# ir_array_final.net
KiCad netlist of a schematic drawn in EAGLE
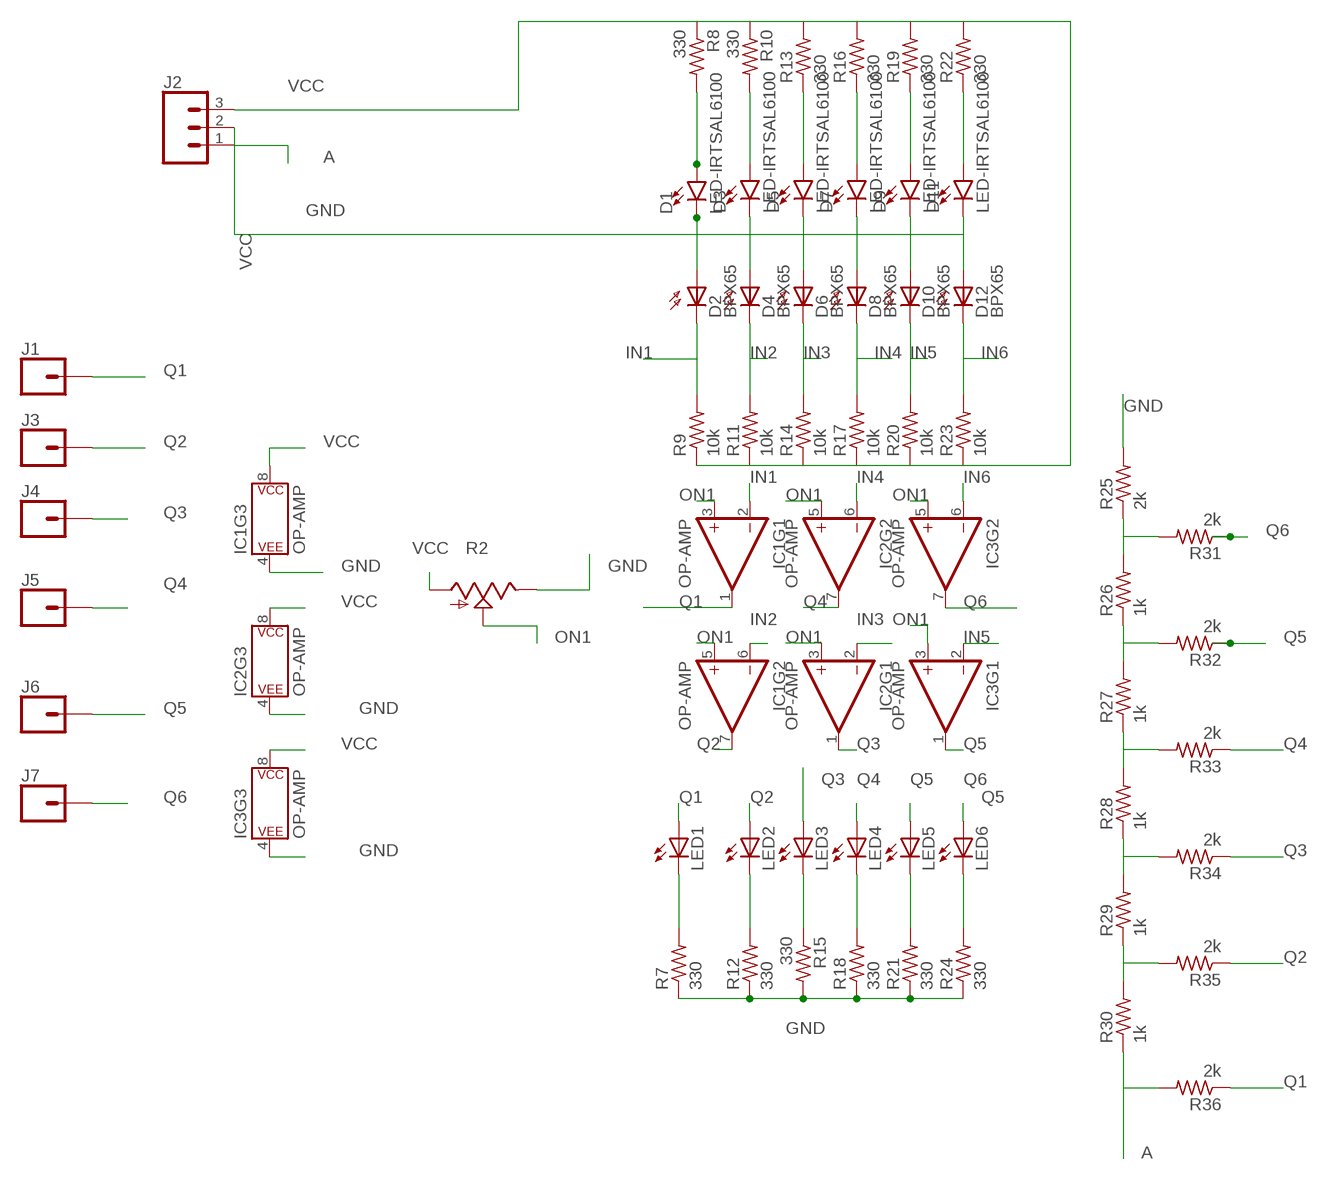
[diagram p0: schematic, sheet 1]

(export (version "E")
  (design (tool "Eeschema 10.0.6"))
  (components
    (comp (ref "D1")
      (value "LED-IRTSAL6100")
      (footprint "eagle-import:LED_5MM")
      (libsource (lib "eagle-import") (part "LED-IRTSAL6100"))
    )
    (comp (ref "D2")
      (value "BPX65")
      (footprint "eagle-import:BPX65")
      (fields (field (name "MPN") "BPX65."))
      (libsource (lib "eagle-import") (part "BPX65"))
    )
    (comp (ref "D3")
      (value "LED-IRTSAL6100")
      (footprint "eagle-import:LED_5MM")
      (libsource (lib "eagle-import") (part "LED-IRTSAL6100"))
    )
    (comp (ref "D4")
      (value "BPX65")
      (footprint "eagle-import:BPX65")
      (fields (field (name "MPN") "BPX65."))
      (libsource (lib "eagle-import") (part "BPX65"))
    )
    (comp (ref "D5")
      (value "LED-IRTSAL6100")
      (footprint "eagle-import:LED_5MM")
      (libsource (lib "eagle-import") (part "LED-IRTSAL6100"))
    )
    (comp (ref "D6")
      (value "BPX65")
      (footprint "eagle-import:BPX65")
      (fields (field (name "MPN") "BPX65."))
      (libsource (lib "eagle-import") (part "BPX65"))
    )
    (comp (ref "D7")
      (value "LED-IRTSAL6100")
      (footprint "eagle-import:LED_5MM")
      (libsource (lib "eagle-import") (part "LED-IRTSAL6100"))
    )
    (comp (ref "D8")
      (value "BPX65")
      (footprint "eagle-import:BPX65")
      (fields (field (name "MPN") "BPX65."))
      (libsource (lib "eagle-import") (part "BPX65"))
    )
    (comp (ref "D9")
      (value "LED-IRTSAL6100")
      (footprint "eagle-import:LED_5MM")
      (libsource (lib "eagle-import") (part "LED-IRTSAL6100"))
    )
    (comp (ref "D10")
      (value "BPX65")
      (footprint "eagle-import:BPX65")
      (fields (field (name "MPN") "BPX65."))
      (libsource (lib "eagle-import") (part "BPX65"))
    )
    (comp (ref "D11")
      (value "LED-IRTSAL6100")
      (footprint "eagle-import:LED_5MM")
      (libsource (lib "eagle-import") (part "LED-IRTSAL6100"))
    )
    (comp (ref "D12")
      (value "BPX65")
      (footprint "eagle-import:BPX65")
      (fields (field (name "MPN") "BPX65."))
      (libsource (lib "eagle-import") (part "BPX65"))
    )
    (comp (ref "IC1")
      (value "OP-AMP")
      (footprint "eagle-import:DIP08")
      (libsource (lib "eagle-import") (part "OPAMP-DUALDIP"))
    )
    (comp (ref "IC2")
      (value "OP-AMP")
      (footprint "eagle-import:DIP08")
      (libsource (lib "eagle-import") (part "OPAMP-DUALDIP"))
    )
    (comp (ref "IC3")
      (value "OP-AMP")
      (footprint "eagle-import:DIP08")
      (libsource (lib "eagle-import") (part "OPAMP-DUALDIP"))
    )
    (comp (ref "J1")
      (value "CONN_01")
      (footprint "eagle-import:1X01")
      (libsource (lib "eagle-import") (part "CONN_01"))
    )
    (comp (ref "J2")
      (value "CONN_03")
      (footprint "eagle-import:1X03")
      (libsource (lib "eagle-import") (part "CONN_03"))
    )
    (comp (ref "J3")
      (value "CONN_01")
      (footprint "eagle-import:1X01")
      (libsource (lib "eagle-import") (part "CONN_01"))
    )
    (comp (ref "J4")
      (value "CONN_01")
      (footprint "eagle-import:1X01")
      (libsource (lib "eagle-import") (part "CONN_01"))
    )
    (comp (ref "J5")
      (value "CONN_01")
      (footprint "eagle-import:1X01")
      (libsource (lib "eagle-import") (part "CONN_01"))
    )
    (comp (ref "J6")
      (value "CONN_01")
      (footprint "eagle-import:1X01")
      (libsource (lib "eagle-import") (part "CONN_01"))
    )
    (comp (ref "J7")
      (value "CONN_01")
      (footprint "eagle-import:1X01")
      (libsource (lib "eagle-import") (part "CONN_01"))
    )
    (comp (ref "LED1")
      (value "LED3MM")
      (footprint "eagle-import:LED3MM")
      (libsource (lib "eagle-import") (part "LED3MM"))
    )
    (comp (ref "LED2")
      (value "LED3MM")
      (footprint "eagle-import:LED3MM")
      (libsource (lib "eagle-import") (part "LED3MM"))
    )
    (comp (ref "LED3")
      (value "LED3MM")
      (footprint "eagle-import:LED3MM")
      (libsource (lib "eagle-import") (part "LED3MM"))
    )
    (comp (ref "LED4")
      (value "LED3MM")
      (footprint "eagle-import:LED3MM")
      (libsource (lib "eagle-import") (part "LED3MM"))
    )
    (comp (ref "LED5")
      (value "LED3MM")
      (footprint "eagle-import:LED3MM")
      (libsource (lib "eagle-import") (part "LED3MM"))
    )
    (comp (ref "LED6")
      (value "LED3MM")
      (footprint "eagle-import:LED3MM")
      (libsource (lib "eagle-import") (part "LED3MM"))
    )
    (comp (ref "R2")
      (value "TRIM_US-CA6V")
      (footprint "eagle-import:CA6V")
      (libsource (lib "eagle-import") (part "TRIM_US-CA6V"))
    )
    (comp (ref "R7")
      (value "330")
      (footprint "eagle-import:0207_9")
      (libsource (lib "eagle-import") (part "R-US_0207/9"))
    )
    (comp (ref "R8")
      (value "330")
      (footprint "eagle-import:0207_9")
      (libsource (lib "eagle-import") (part "R-US_0207/9"))
    )
    (comp (ref "R9")
      (value "10k")
      (footprint "eagle-import:0207_9")
      (libsource (lib "eagle-import") (part "R-US_0207/9"))
    )
    (comp (ref "R10")
      (value "330")
      (footprint "eagle-import:0207_9")
      (libsource (lib "eagle-import") (part "R-US_0207/9"))
    )
    (comp (ref "R11")
      (value "10k")
      (footprint "eagle-import:0207_9")
      (libsource (lib "eagle-import") (part "R-US_0207/9"))
    )
    (comp (ref "R12")
      (value "330")
      (footprint "eagle-import:0207_9")
      (libsource (lib "eagle-import") (part "R-US_0207/9"))
    )
    (comp (ref "R13")
      (value "330")
      (footprint "eagle-import:0207_9")
      (libsource (lib "eagle-import") (part "R-US_0207/9"))
    )
    (comp (ref "R14")
      (value "10k")
      (footprint "eagle-import:0207_9")
      (libsource (lib "eagle-import") (part "R-US_0207/9"))
    )
    (comp (ref "R15")
      (value "330")
      (footprint "eagle-import:0207_9")
      (libsource (lib "eagle-import") (part "R-US_0207/9"))
    )
    (comp (ref "R16")
      (value "330")
      (footprint "eagle-import:0207_9")
      (libsource (lib "eagle-import") (part "R-US_0207/9"))
    )
    (comp (ref "R17")
      (value "10k")
      (footprint "eagle-import:0207_9")
      (libsource (lib "eagle-import") (part "R-US_0207/9"))
    )
    (comp (ref "R18")
      (value "330")
      (footprint "eagle-import:0207_9")
      (libsource (lib "eagle-import") (part "R-US_0207/9"))
    )
    (comp (ref "R19")
      (value "330")
      (footprint "eagle-import:0207_9")
      (libsource (lib "eagle-import") (part "R-US_0207/9"))
    )
    (comp (ref "R20")
      (value "10k")
      (footprint "eagle-import:0207_9")
      (libsource (lib "eagle-import") (part "R-US_0207/9"))
    )
    (comp (ref "R21")
      (value "330")
      (footprint "eagle-import:0207_9")
      (libsource (lib "eagle-import") (part "R-US_0207/9"))
    )
    (comp (ref "R22")
      (value "330")
      (footprint "eagle-import:0207_9")
      (libsource (lib "eagle-import") (part "R-US_0207/9"))
    )
    (comp (ref "R23")
      (value "10k")
      (footprint "eagle-import:0207_9")
      (libsource (lib "eagle-import") (part "R-US_0207/9"))
    )
    (comp (ref "R24")
      (value "330")
      (footprint "eagle-import:0207_9")
      (libsource (lib "eagle-import") (part "R-US_0207/9"))
    )
    (comp (ref "R25")
      (value "2k")
      (footprint "eagle-import:0207_9")
      (libsource (lib "eagle-import") (part "R-US_0207/9"))
    )
    (comp (ref "R26")
      (value "1k")
      (footprint "eagle-import:0207_9")
      (libsource (lib "eagle-import") (part "R-US_0207/9"))
    )
    (comp (ref "R27")
      (value "1k")
      (footprint "eagle-import:0207_9")
      (libsource (lib "eagle-import") (part "R-US_0207/9"))
    )
    (comp (ref "R28")
      (value "1k")
      (footprint "eagle-import:0207_9")
      (libsource (lib "eagle-import") (part "R-US_0207/9"))
    )
    (comp (ref "R29")
      (value "1k")
      (footprint "eagle-import:0207_9")
      (libsource (lib "eagle-import") (part "R-US_0207/9"))
    )
    (comp (ref "R30")
      (value "1k")
      (footprint "eagle-import:0207_9")
      (libsource (lib "eagle-import") (part "R-US_0207/9"))
    )
    (comp (ref "R31")
      (value "2k")
      (footprint "eagle-import:0207_9")
      (libsource (lib "eagle-import") (part "R-US_0207/9"))
    )
    (comp (ref "R32")
      (value "2k")
      (footprint "eagle-import:0207_9")
      (libsource (lib "eagle-import") (part "R-US_0207/9"))
    )
    (comp (ref "R33")
      (value "2k")
      (footprint "eagle-import:0207_9")
      (libsource (lib "eagle-import") (part "R-US_0207/9"))
    )
    (comp (ref "R34")
      (value "2k")
      (footprint "eagle-import:0207_9")
      (libsource (lib "eagle-import") (part "R-US_0207/9"))
    )
    (comp (ref "R35")
      (value "2k")
      (footprint "eagle-import:0207_9")
      (libsource (lib "eagle-import") (part "R-US_0207/9"))
    )
    (comp (ref "R36")
      (value "2k")
      (footprint "eagle-import:0207_9")
      (libsource (lib "eagle-import") (part "R-US_0207/9"))
    )
  )
  (nets
    (net (code "1") (name "/A") (class "Default")
      (node (ref "J2") (pin "1") (pinfunction "1_1") (pintype "passive"))
      (node (ref "R30") (pin "1") (pinfunction "1_1") (pintype "passive"))
      (node (ref "R36") (pin "2") (pinfunction "2_2") (pintype "passive"))
    )
    (net (code "2") (name "/GND") (class "Default")
      (node (ref "D1") (pin "K") (pinfunction "C_K") (pintype "passive"))
      (node (ref "D10") (pin "A") (pinfunction "A_A") (pintype "passive"))
      (node (ref "D11") (pin "K") (pinfunction "C_K") (pintype "passive"))
      (node (ref "D12") (pin "A") (pinfunction "A_A") (pintype "passive"))
      (node (ref "D2") (pin "A") (pinfunction "A_A") (pintype "passive"))
      (node (ref "D3") (pin "K") (pinfunction "C_K") (pintype "passive"))
      (node (ref "D4") (pin "A") (pinfunction "A_A") (pintype "passive"))
      (node (ref "D5") (pin "K") (pinfunction "C_K") (pintype "passive"))
      (node (ref "D6") (pin "A") (pinfunction "A_A") (pintype "passive"))
      (node (ref "D7") (pin "K") (pinfunction "C_K") (pintype "passive"))
      (node (ref "D8") (pin "A") (pinfunction "A_A") (pintype "passive"))
      (node (ref "D9") (pin "K") (pinfunction "C_K") (pintype "passive"))
      (node (ref "IC1") (pin "4") (pinfunction "P$V-_4") (pintype "bidirectional"))
      (node (ref "IC2") (pin "4") (pinfunction "P$V-_4") (pintype "bidirectional"))
      (node (ref "IC3") (pin "4") (pinfunction "P$V-_4") (pintype "bidirectional"))
      (node (ref "J2") (pin "2") (pinfunction "2_2") (pintype "passive"))
      (node (ref "R12") (pin "1") (pinfunction "1_1") (pintype "passive"))
      (node (ref "R15") (pin "2") (pinfunction "2_2") (pintype "passive"))
      (node (ref "R18") (pin "1") (pinfunction "1_1") (pintype "passive"))
      (node (ref "R2") (pin "E") (pinfunction "E_E") (pintype "passive"))
      (node (ref "R21") (pin "1") (pinfunction "1_1") (pintype "passive"))
      (node (ref "R24") (pin "1") (pinfunction "1_1") (pintype "passive"))
      (node (ref "R25") (pin "2") (pinfunction "2_2") (pintype "passive"))
      (node (ref "R7") (pin "1") (pinfunction "1_1") (pintype "passive"))
    )
    (net (code "3") (name "/IN1") (class "Default")
      (node (ref "D2") (pin "K") (pinfunction "C_K") (pintype "passive"))
      (node (ref "IC1") (pin "2") (pinfunction "-IN_2") (pintype "input"))
      (node (ref "R9") (pin "2") (pinfunction "2_2") (pintype "passive"))
    )
    (net (code "4") (name "/IN2") (class "Default")
      (node (ref "D4") (pin "K") (pinfunction "C_K") (pintype "passive"))
      (node (ref "IC1") (pin "6") (pinfunction "-IN_6") (pintype "input"))
      (node (ref "R11") (pin "2") (pinfunction "2_2") (pintype "passive"))
    )
    (net (code "5") (name "/IN3") (class "Default")
      (node (ref "D6") (pin "K") (pinfunction "C_K") (pintype "passive"))
      (node (ref "IC2") (pin "2") (pinfunction "-IN_2") (pintype "input"))
      (node (ref "R14") (pin "2") (pinfunction "2_2") (pintype "passive"))
    )
    (net (code "6") (name "/IN4") (class "Default")
      (node (ref "D8") (pin "K") (pinfunction "C_K") (pintype "passive"))
      (node (ref "IC2") (pin "6") (pinfunction "-IN_6") (pintype "input"))
      (node (ref "R17") (pin "2") (pinfunction "2_2") (pintype "passive"))
    )
    (net (code "7") (name "/IN5") (class "Default")
      (node (ref "D10") (pin "K") (pinfunction "C_K") (pintype "passive"))
      (node (ref "IC3") (pin "2") (pinfunction "-IN_2") (pintype "input"))
      (node (ref "R20") (pin "2") (pinfunction "2_2") (pintype "passive"))
    )
    (net (code "8") (name "/IN6") (class "Default")
      (node (ref "D12") (pin "K") (pinfunction "C_K") (pintype "passive"))
      (node (ref "IC3") (pin "6") (pinfunction "-IN_6") (pintype "input"))
      (node (ref "R23") (pin "2") (pinfunction "2_2") (pintype "passive"))
    )
    (net (code "9") (name "/ON1") (class "Default")
      (node (ref "IC1") (pin "3") (pinfunction "+IN_3") (pintype "input"))
      (node (ref "IC1") (pin "5") (pinfunction "+IN_5") (pintype "input"))
      (node (ref "IC2") (pin "3") (pinfunction "+IN_3") (pintype "input"))
      (node (ref "IC2") (pin "5") (pinfunction "+IN_5") (pintype "input"))
      (node (ref "IC3") (pin "3") (pinfunction "+IN_3") (pintype "input"))
      (node (ref "IC3") (pin "5") (pinfunction "+IN_5") (pintype "input"))
      (node (ref "R2") (pin "S") (pinfunction "S_S") (pintype "passive"))
    )
    (net (code "10") (name "/Q1") (class "Default")
      (node (ref "IC1") (pin "1") (pinfunction "OUT_1") (pintype "output"))
      (node (ref "J1") (pin "1") (pinfunction "1_1") (pintype "passive"))
      (node (ref "LED1") (pin "A") (pinfunction "A_A") (pintype "passive"))
      (node (ref "R36") (pin "1") (pinfunction "1_1") (pintype "passive"))
    )
    (net (code "11") (name "/Q2") (class "Default")
      (node (ref "IC1") (pin "7") (pinfunction "OUT_7") (pintype "output"))
      (node (ref "J3") (pin "1") (pinfunction "1_1") (pintype "passive"))
      (node (ref "LED2") (pin "A") (pinfunction "A_A") (pintype "passive"))
      (node (ref "R35") (pin "1") (pinfunction "1_1") (pintype "passive"))
    )
    (net (code "12") (name "/Q3") (class "Default")
      (node (ref "IC2") (pin "1") (pinfunction "OUT_1") (pintype "output"))
      (node (ref "J4") (pin "1") (pinfunction "1_1") (pintype "passive"))
      (node (ref "LED3") (pin "A") (pinfunction "A_A") (pintype "passive"))
      (node (ref "R34") (pin "1") (pinfunction "1_1") (pintype "passive"))
    )
    (net (code "13") (name "/Q4") (class "Default")
      (node (ref "IC2") (pin "7") (pinfunction "OUT_7") (pintype "output"))
      (node (ref "J5") (pin "1") (pinfunction "1_1") (pintype "passive"))
      (node (ref "LED4") (pin "A") (pinfunction "A_A") (pintype "passive"))
      (node (ref "R33") (pin "1") (pinfunction "1_1") (pintype "passive"))
    )
    (net (code "14") (name "/Q5") (class "Default")
      (node (ref "IC3") (pin "1") (pinfunction "OUT_1") (pintype "output"))
      (node (ref "J6") (pin "1") (pinfunction "1_1") (pintype "passive"))
      (node (ref "LED5") (pin "A") (pinfunction "A_A") (pintype "passive"))
      (node (ref "R32") (pin "1") (pinfunction "1_1") (pintype "passive"))
    )
    (net (code "15") (name "/Q6") (class "Default")
      (node (ref "IC3") (pin "7") (pinfunction "OUT_7") (pintype "output"))
      (node (ref "J7") (pin "1") (pinfunction "1_1") (pintype "passive"))
      (node (ref "LED6") (pin "A") (pinfunction "A_A") (pintype "passive"))
      (node (ref "R31") (pin "1") (pinfunction "1_1") (pintype "passive"))
    )
    (net (code "16") (name "/VCC") (class "Default")
      (node (ref "IC1") (pin "8") (pinfunction "P$V+_8") (pintype "bidirectional"))
      (node (ref "IC2") (pin "8") (pinfunction "P$V+_8") (pintype "bidirectional"))
      (node (ref "IC3") (pin "8") (pinfunction "P$V+_8") (pintype "bidirectional"))
      (node (ref "J2") (pin "3") (pinfunction "3_3") (pintype "passive"))
      (node (ref "R10") (pin "1") (pinfunction "1_1") (pintype "passive"))
      (node (ref "R11") (pin "1") (pinfunction "1_1") (pintype "passive"))
      (node (ref "R13") (pin "2") (pinfunction "2_2") (pintype "passive"))
      (node (ref "R14") (pin "1") (pinfunction "1_1") (pintype "passive"))
      (node (ref "R16") (pin "2") (pinfunction "2_2") (pintype "passive"))
      (node (ref "R17") (pin "1") (pinfunction "1_1") (pintype "passive"))
      (node (ref "R19") (pin "2") (pinfunction "2_2") (pintype "passive"))
      (node (ref "R2") (pin "A") (pinfunction "A_A") (pintype "passive"))
      (node (ref "R20") (pin "1") (pinfunction "1_1") (pintype "passive"))
      (node (ref "R22") (pin "2") (pinfunction "2_2") (pintype "passive"))
      (node (ref "R23") (pin "1") (pinfunction "1_1") (pintype "passive"))
      (node (ref "R8") (pin "1") (pinfunction "1_1") (pintype "passive"))
      (node (ref "R9") (pin "1") (pinfunction "1_1") (pintype "passive"))
    )
    (net (code "17") (name "Net-(D1-PadA)") (class "Default")
      (node (ref "D1") (pin "A") (pinfunction "A_A") (pintype "passive"))
      (node (ref "R8") (pin "2") (pinfunction "2_2") (pintype "passive"))
    )
    (net (code "18") (name "Net-(D3-PadA)") (class "Default")
      (node (ref "D3") (pin "A") (pinfunction "A_A") (pintype "passive"))
      (node (ref "R10") (pin "2") (pinfunction "2_2") (pintype "passive"))
    )
    (net (code "19") (name "Net-(D5-PadA)") (class "Default")
      (node (ref "D5") (pin "A") (pinfunction "A_A") (pintype "passive"))
      (node (ref "R13") (pin "1") (pinfunction "1_1") (pintype "passive"))
    )
    (net (code "20") (name "Net-(D7-PadA)") (class "Default")
      (node (ref "D7") (pin "A") (pinfunction "A_A") (pintype "passive"))
      (node (ref "R16") (pin "1") (pinfunction "1_1") (pintype "passive"))
    )
    (net (code "21") (name "Net-(D9-PadA)") (class "Default")
      (node (ref "D9") (pin "A") (pinfunction "A_A") (pintype "passive"))
      (node (ref "R19") (pin "1") (pinfunction "1_1") (pintype "passive"))
    )
    (net (code "22") (name "Net-(D11-PadA)") (class "Default")
      (node (ref "D11") (pin "A") (pinfunction "A_A") (pintype "passive"))
      (node (ref "R22") (pin "1") (pinfunction "1_1") (pintype "passive"))
    )
    (net (code "23") (name "Net-(LED1-C)") (class "Default")
      (node (ref "LED1") (pin "K") (pinfunction "C_K") (pintype "passive"))
      (node (ref "R7") (pin "2") (pinfunction "2_2") (pintype "passive"))
    )
    (net (code "24") (name "Net-(LED2-C)") (class "Default")
      (node (ref "LED2") (pin "K") (pinfunction "C_K") (pintype "passive"))
      (node (ref "R12") (pin "2") (pinfunction "2_2") (pintype "passive"))
    )
    (net (code "25") (name "Net-(LED3-C)") (class "Default")
      (node (ref "LED3") (pin "K") (pinfunction "C_K") (pintype "passive"))
      (node (ref "R15") (pin "1") (pinfunction "1_1") (pintype "passive"))
    )
    (net (code "26") (name "Net-(LED4-C)") (class "Default")
      (node (ref "LED4") (pin "K") (pinfunction "C_K") (pintype "passive"))
      (node (ref "R18") (pin "2") (pinfunction "2_2") (pintype "passive"))
    )
    (net (code "27") (name "Net-(LED5-C)") (class "Default")
      (node (ref "LED5") (pin "K") (pinfunction "C_K") (pintype "passive"))
      (node (ref "R21") (pin "2") (pinfunction "2_2") (pintype "passive"))
    )
    (net (code "28") (name "Net-(LED6-C)") (class "Default")
      (node (ref "LED6") (pin "K") (pinfunction "C_K") (pintype "passive"))
      (node (ref "R24") (pin "2") (pinfunction "2_2") (pintype "passive"))
    )
    (net (code "29") (name "Net-(R25-Pad1)") (class "Default")
      (node (ref "R25") (pin "1") (pinfunction "1_1") (pintype "passive"))
      (node (ref "R26") (pin "2") (pinfunction "2_2") (pintype "passive"))
      (node (ref "R31") (pin "2") (pinfunction "2_2") (pintype "passive"))
    )
    (net (code "30") (name "Net-(R26-Pad1)") (class "Default")
      (node (ref "R26") (pin "1") (pinfunction "1_1") (pintype "passive"))
      (node (ref "R27") (pin "2") (pinfunction "2_2") (pintype "passive"))
      (node (ref "R32") (pin "2") (pinfunction "2_2") (pintype "passive"))
    )
    (net (code "31") (name "Net-(R27-Pad1)") (class "Default")
      (node (ref "R27") (pin "1") (pinfunction "1_1") (pintype "passive"))
      (node (ref "R28") (pin "2") (pinfunction "2_2") (pintype "passive"))
      (node (ref "R33") (pin "2") (pinfunction "2_2") (pintype "passive"))
    )
    (net (code "32") (name "Net-(R28-Pad1)") (class "Default")
      (node (ref "R28") (pin "1") (pinfunction "1_1") (pintype "passive"))
      (node (ref "R29") (pin "2") (pinfunction "2_2") (pintype "passive"))
      (node (ref "R34") (pin "2") (pinfunction "2_2") (pintype "passive"))
    )
    (net (code "33") (name "Net-(R29-Pad1)") (class "Default")
      (node (ref "R29") (pin "1") (pinfunction "1_1") (pintype "passive"))
      (node (ref "R30") (pin "2") (pinfunction "2_2") (pintype "passive"))
      (node (ref "R35") (pin "2") (pinfunction "2_2") (pintype "passive"))
    )
  )
)
